# untitled01.net
KiCad netlist of a schematic drawn in EAGLE
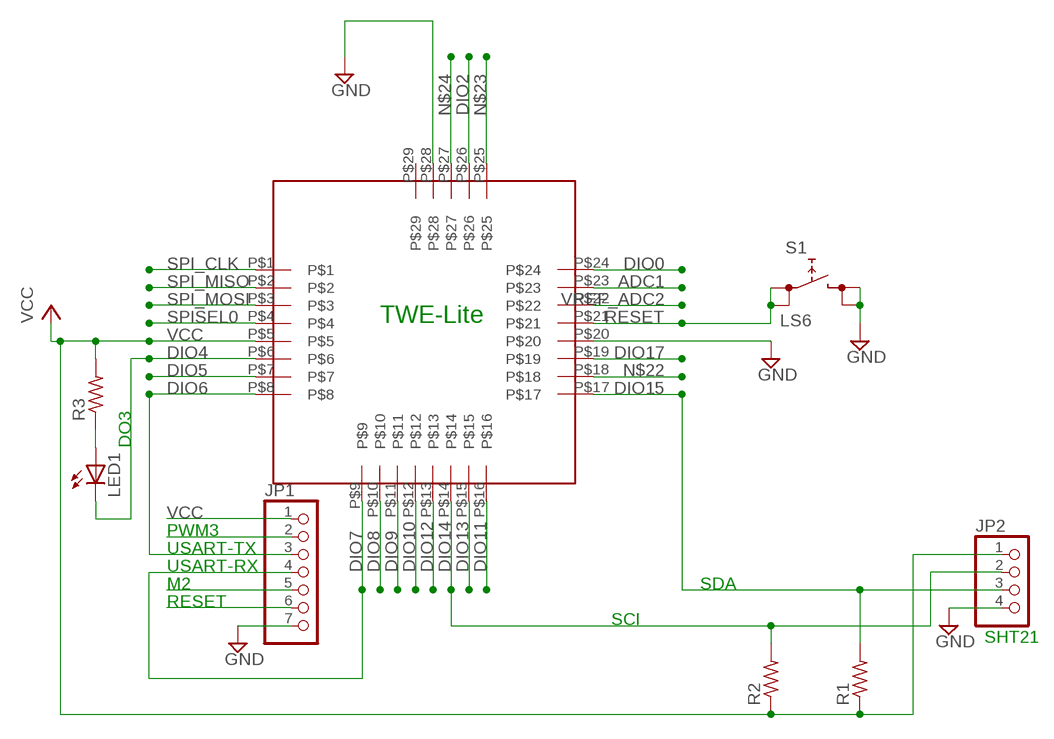
[diagram p0: schematic, sheet 1]
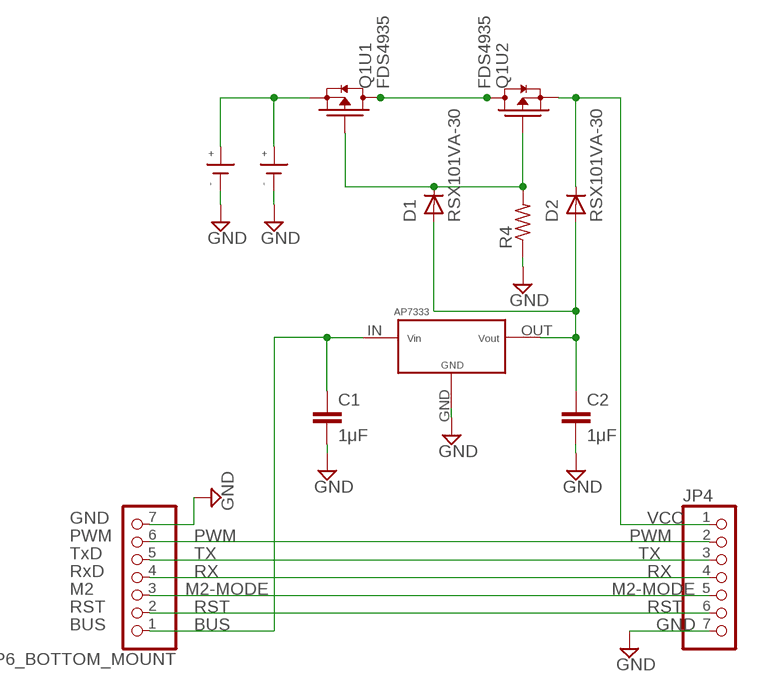
[diagram p1: schematic, sheet 2]
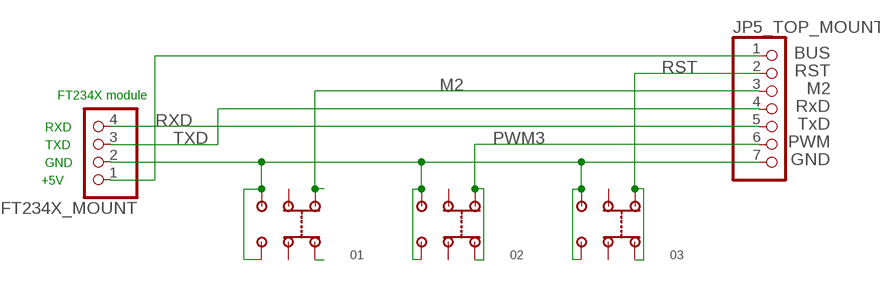
[diagram p2: schematic, sheet 3]

(export (version "E")
  (design (tool "Eeschema 10.0.6"))
  (components
    (comp (ref "01")
      (value "SSSS213202")
      (footprint "eagle-import:SSSS213202")
      (libsource (lib "eagle-import") (part "SSSS213202"))
    )
    (comp (ref "02")
      (value "SSSS213202")
      (footprint "eagle-import:SSSS213202")
      (libsource (lib "eagle-import") (part "SSSS213202"))
    )
    (comp (ref "03")
      (value "SSSS213202")
      (footprint "eagle-import:SSSS213202")
      (libsource (lib "eagle-import") (part "SSSS213202"))
    )
    (comp (ref "FT234X_MOUNT")
      (value "PINHD-1X4")
      (footprint "eagle-import:1X04")
      (libsource (lib "eagle-import") (part "PINHD-1X4"))
    )
    (comp (ref "JP5_TOP_MOUNT")
      (value "PINHD-1X7")
      (footprint "eagle-import:1X07")
      (libsource (lib "eagle-import") (part "PINHD-1X7"))
    )
    (comp (ref "JP1")
      (value "PINHD-1X7")
      (footprint "eagle-import:1X07")
      (libsource (lib "eagle-import") (part "PINHD-1X7"))
    )
    (comp (ref "JP2")
      (value "PINHD-1X4/90")
      (footprint "eagle-import:1X04_90")
      (libsource (lib "eagle-import") (part "pinhead_325_PINHD-1X4/90"))
    )
    (comp (ref "LED1")
      (value "LEDCHIP-LED0603")
      (footprint "eagle-import:CHIP-LED0603")
      (libsource (lib "eagle-import") (part "LEDCHIP-LED0603"))
    )
    (comp (ref "R1")
      (value "R-US_R0805")
      (footprint "eagle-import:R0805")
      (libsource (lib "eagle-import") (part "R-US_R0805"))
    )
    (comp (ref "R2")
      (value "R-US_R0805")
      (footprint "eagle-import:R0805")
      (libsource (lib "eagle-import") (part "R-US_R0805"))
    )
    (comp (ref "R3")
      (value "R-US_R0805")
      (footprint "eagle-import:R0805")
      (libsource (lib "eagle-import") (part "R-US_R0805"))
    )
    (comp (ref "S1")
      (value "LS6")
      (footprint "eagle-import:LS6")
      (libsource (lib "eagle-import") (part "LS6"))
    )
    (comp (ref "U$1")
      (value "LITE")
      (footprint "eagle-import:LITE")
      (libsource (lib "eagle-import") (part "LITE"))
    )
    (comp (ref "C1")
      (value "1μF")
      (footprint "eagle-import:C1608")
      (libsource (lib "eagle-import") (part "C-EUC1608"))
    )
    (comp (ref "C2")
      (value "1μF")
      (footprint "eagle-import:C1608")
      (libsource (lib "eagle-import") (part "C-EUC1608"))
    )
    (comp (ref "D1")
      (value "RSX101VA-30")
      (footprint "eagle-import:RSX101VA")
      (libsource (lib "eagle-import") (part "RSX101VA-30"))
    )
    (comp (ref "D2")
      (value "RSX101VA-30")
      (footprint "eagle-import:RSX101VA")
      (libsource (lib "eagle-import") (part "RSX101VA-30"))
    )
    (comp (ref "JP4")
      (value "PINHD-1X7")
      (footprint "eagle-import:1X07")
      (libsource (lib "eagle-import") (part "PINHD-1X7"))
    )
    (comp (ref "JP6_BOTTOM_MOUNT")
      (value "PINHD-1X7")
      (footprint "eagle-import:1X07")
      (libsource (lib "eagle-import") (part "PINHD-1X7"))
    )
    (comp (ref "Q1")
      (value "FDS4935")
      (footprint "eagle-import:SOIC(8PIN)")
      (libsource (lib "eagle-import") (part "FDS4935"))
    )
    (comp (ref "R4")
      (value "R-US_M0805")
      (footprint "eagle-import:M0805")
      (libsource (lib "eagle-import") (part "resistor_348_R-US_M0805"))
    )
    (comp (ref "U$2")
      (value "CH004-2032LF")
      (footprint "eagle-import:CH004-2032LF")
      (libsource (lib "eagle-import") (part "CH004-2032LF"))
    )
    (comp (ref "U$3")
      (value "CH004-2032LF")
      (footprint "eagle-import:CH004-2032LF")
      (libsource (lib "eagle-import") (part "CH004-2032LF"))
    )
    (comp (ref "U$5")
      (value "AP7333_SOT-23")
      (footprint "eagle-import:AP7333_SOT-23")
      (libsource (lib "eagle-import") (part "AP7333_SOT-23"))
    )
  )
  (nets
    (net (code "1") (name "ADC1") (class "Default")
      (node (ref "U$1") (pin "P$23") (pinfunction "P$23_P$23") (pintype "bidirectional"))
    )
    (net (code "2") (name "BUS") (class "Default")
      (node (ref "C1") (pin "1") (pinfunction "1_1") (pintype "passive"))
      (node (ref "JP6_BOTTOM_MOUNT") (pin "1") (pinfunction "1_1") (pintype "passive"))
      (node (ref "U$5") (pin "IN") (pinfunction "IN_IN") (pintype "input"))
    )
    (net (code "3") (name "DIO0") (class "Default")
      (node (ref "U$1") (pin "P$24") (pinfunction "P$24_P$24") (pintype "bidirectional"))
    )
    (net (code "4") (name "DIO2") (class "Default")
      (node (ref "JP1") (pin "5") (pinfunction "5_5") (pintype "passive"))
      (node (ref "U$1") (pin "P$26") (pinfunction "P$26_P$26") (pintype "bidirectional"))
    )
    (net (code "5") (name "DIO4") (class "Default")
      (node (ref "LED1") (pin "C") (pinfunction "C_C") (pintype "passive"))
      (node (ref "U$1") (pin "P$6") (pinfunction "P$6_P$6") (pintype "bidirectional"))
    )
    (net (code "6") (name "DIO5") (class "Default")
      (node (ref "U$1") (pin "P$7") (pinfunction "P$7_P$7") (pintype "bidirectional"))
    )
    (net (code "7") (name "DIO6") (class "Default")
      (node (ref "JP1") (pin "3") (pinfunction "3_3") (pintype "passive"))
      (node (ref "U$1") (pin "P$8") (pinfunction "P$8_P$8") (pintype "bidirectional"))
    )
    (net (code "8") (name "DIO7") (class "Default")
      (node (ref "JP1") (pin "4") (pinfunction "4_4") (pintype "passive"))
      (node (ref "U$1") (pin "P$9") (pinfunction "P$9_P$9") (pintype "bidirectional"))
    )
    (net (code "9") (name "DIO8") (class "Default")
      (node (ref "U$1") (pin "P$10") (pinfunction "P$10_P$10") (pintype "bidirectional"))
    )
    (net (code "10") (name "DIO9") (class "Default")
      (node (ref "U$1") (pin "P$11") (pinfunction "P$11_P$11") (pintype "bidirectional"))
    )
    (net (code "11") (name "DIO10") (class "Default")
      (node (ref "U$1") (pin "P$12") (pinfunction "P$12_P$12") (pintype "bidirectional"))
    )
    (net (code "12") (name "DIO11") (class "Default")
      (node (ref "U$1") (pin "P$16") (pinfunction "P$16_P$16") (pintype "bidirectional"))
    )
    (net (code "13") (name "DIO12") (class "Default")
      (node (ref "U$1") (pin "P$13") (pinfunction "P$13_P$13") (pintype "bidirectional"))
    )
    (net (code "14") (name "DIO13") (class "Default")
      (node (ref "U$1") (pin "P$15") (pinfunction "P$15_P$15") (pintype "bidirectional"))
    )
    (net (code "15") (name "DIO14") (class "Default")
      (node (ref "JP2") (pin "2") (pinfunction "2_2") (pintype "passive"))
      (node (ref "R2") (pin "2") (pinfunction "2_2") (pintype "passive"))
      (node (ref "U$1") (pin "P$14") (pinfunction "P$14_P$14") (pintype "bidirectional"))
    )
    (net (code "16") (name "DIO15") (class "Default")
      (node (ref "JP2") (pin "3") (pinfunction "3_3") (pintype "passive"))
      (node (ref "R1") (pin "2") (pinfunction "2_2") (pintype "passive"))
      (node (ref "U$1") (pin "P$17") (pinfunction "P$17_P$17") (pintype "bidirectional"))
    )
    (net (code "17") (name "DIO17") (class "Default")
      (node (ref "U$1") (pin "P$19") (pinfunction "P$19_P$19") (pintype "bidirectional"))
    )
    (net (code "18") (name "GND") (class "Default")
      (node (ref "01") (pin "3-1") (pinfunction "3-1_3-1") (pintype "bidirectional"))
      (node (ref "01") (pin "3-2") (pinfunction "3-2_3-2") (pintype "bidirectional"))
      (node (ref "02") (pin "3-1") (pinfunction "3-1_3-1") (pintype "bidirectional"))
      (node (ref "02") (pin "3-2") (pinfunction "3-2_3-2") (pintype "bidirectional"))
      (node (ref "03") (pin "3-1") (pinfunction "3-1_3-1") (pintype "bidirectional"))
      (node (ref "03") (pin "3-2") (pinfunction "3-2_3-2") (pintype "bidirectional"))
      (node (ref "C1") (pin "2") (pinfunction "2_2") (pintype "passive"))
      (node (ref "C2") (pin "2") (pinfunction "2_2") (pintype "passive"))
      (node (ref "FT234X_MOUNT") (pin "2") (pinfunction "2_2") (pintype "passive"))
      (node (ref "JP1") (pin "7") (pinfunction "7_7") (pintype "passive"))
      (node (ref "JP2") (pin "4") (pinfunction "4_4") (pintype "passive"))
      (node (ref "JP4") (pin "7") (pinfunction "7_7") (pintype "passive"))
      (node (ref "JP5_TOP_MOUNT") (pin "7") (pinfunction "7_7") (pintype "passive"))
      (node (ref "JP6_BOTTOM_MOUNT") (pin "7") (pinfunction "7_7") (pintype "passive"))
      (node (ref "R4") (pin "1") (pinfunction "1_1") (pintype "passive"))
      (node (ref "S1") (pin "P$3") (pinfunction "1_P$3") (pintype "passive"))
      (node (ref "S1") (pin "P$4") (pinfunction "1_P$4") (pintype "passive"))
      (node (ref "U$1") (pin "P$20") (pinfunction "P$20_P$20") (pintype "bidirectional"))
      (node (ref "U$1") (pin "P$28") (pinfunction "P$28_P$28") (pintype "bidirectional"))
      (node (ref "U$2") (pin "-") (pinfunction "-_-") (pintype "bidirectional"))
      (node (ref "U$3") (pin "-") (pinfunction "-_-") (pintype "bidirectional"))
      (node (ref "U$5") (pin "GND") (pinfunction "GND_GND") (pintype "bidirectional"))
    )
    (net (code "19") (name "M2") (class "Default")
      (node (ref "01") (pin "1-2") (pinfunction "1-2_1-2") (pintype "bidirectional"))
      (node (ref "JP5_TOP_MOUNT") (pin "3") (pinfunction "3_3") (pintype "passive"))
    )
    (net (code "20") (name "M2-MODE") (class "Default")
      (node (ref "JP4") (pin "5") (pinfunction "5_5") (pintype "passive"))
      (node (ref "JP6_BOTTOM_MOUNT") (pin "3") (pinfunction "3_3") (pintype "passive"))
    )
    (net (code "21") (name "N$22") (class "Default")
      (node (ref "U$1") (pin "P$18") (pinfunction "P$18_P$18") (pintype "bidirectional"))
    )
    (net (code "22") (name "N$23") (class "Default")
      (node (ref "U$1") (pin "P$25") (pinfunction "P$25_P$25") (pintype "bidirectional"))
    )
    (net (code "23") (name "N$24") (class "Default")
      (node (ref "U$1") (pin "P$27") (pinfunction "P$27_P$27") (pintype "bidirectional"))
    )
    (net (code "24") (name "Net-(D1-A)") (class "Default")
      (node (ref "C2") (pin "1") (pinfunction "1_1") (pintype "passive"))
      (node (ref "D1") (pin "ANODE") (pinfunction "A_ANODE") (pintype "passive"))
      (node (ref "D2") (pin "ANODE") (pinfunction "A_ANODE") (pintype "passive"))
      (node (ref "U$5") (pin "OUT") (pinfunction "OUT_OUT") (pintype "output"))
    )
    (net (code "25") (name "Net-(D1-C)") (class "Default")
      (node (ref "D1") (pin "CATHODE") (pinfunction "C_CATHODE") (pintype "passive"))
      (node (ref "Q1") (pin "2") (pinfunction "G_2") (pintype "passive"))
      (node (ref "Q1") (pin "4") (pinfunction "G_4") (pintype "passive"))
      (node (ref "R4") (pin "2") (pinfunction "2_2") (pintype "passive"))
    )
    (net (code "26") (name "Net-(FT234X_MOUNT-Pad1)") (class "Default")
      (node (ref "FT234X_MOUNT") (pin "1") (pinfunction "1_1") (pintype "passive"))
      (node (ref "JP5_TOP_MOUNT") (pin "1") (pinfunction "1_1") (pintype "passive"))
    )
    (net (code "27") (name "Net-(LED1-PadA)") (class "Default")
      (node (ref "LED1") (pin "A") (pinfunction "A_A") (pintype "passive"))
      (node (ref "R3") (pin "1") (pinfunction "1_1") (pintype "passive"))
    )
    (net (code "28") (name "Net-(Q1A-D1)") (class "Default")
      (node (ref "Q1") (pin "5") (pinfunction "D2_5") (pintype "passive"))
      (node (ref "Q1") (pin "6") (pinfunction "D1_6") (pintype "passive"))
      (node (ref "Q1") (pin "7") (pinfunction "D2_7") (pintype "passive"))
      (node (ref "Q1") (pin "8") (pinfunction "D1_8") (pintype "passive"))
    )
    (net (code "29") (name "Net-(Q1A-S)") (class "Default")
      (node (ref "Q1") (pin "1") (pinfunction "S_1") (pintype "passive"))
      (node (ref "U$2") (pin "+") (pinfunction "+_+") (pintype "bidirectional"))
      (node (ref "U$3") (pin "+") (pinfunction "+_+") (pintype "bidirectional"))
    )
    (net (code "30") (name "PWM") (class "Default")
      (node (ref "JP4") (pin "2") (pinfunction "2_2") (pintype "passive"))
      (node (ref "JP6_BOTTOM_MOUNT") (pin "6") (pinfunction "6_6") (pintype "passive"))
    )
    (net (code "31") (name "PWM3") (class "Default")
      (node (ref "02") (pin "1-1") (pinfunction "1-1_1-1") (pintype "bidirectional"))
      (node (ref "02") (pin "1-2") (pinfunction "1-2_1-2") (pintype "bidirectional"))
      (node (ref "JP5_TOP_MOUNT") (pin "6") (pinfunction "6_6") (pintype "passive"))
    )
    (net (code "32") (name "RESET") (class "Default")
      (node (ref "JP1") (pin "6") (pinfunction "6_6") (pintype "passive"))
      (node (ref "S1") (pin "P$1") (pinfunction "0_P$1") (pintype "passive"))
      (node (ref "S1") (pin "P$2") (pinfunction "0_P$2") (pintype "passive"))
      (node (ref "U$1") (pin "P$21") (pinfunction "P$21_P$21") (pintype "bidirectional"))
    )
    (net (code "33") (name "RST") (class "Default")
      (node (ref "03") (pin "1-1") (pinfunction "1-1_1-1") (pintype "bidirectional"))
      (node (ref "03") (pin "1-2") (pinfunction "1-2_1-2") (pintype "bidirectional"))
      (node (ref "JP4") (pin "6") (pinfunction "6_6") (pintype "passive"))
      (node (ref "JP5_TOP_MOUNT") (pin "2") (pinfunction "2_2") (pintype "passive"))
      (node (ref "JP6_BOTTOM_MOUNT") (pin "2") (pinfunction "2_2") (pintype "passive"))
    )
    (net (code "34") (name "RX") (class "Default")
      (node (ref "JP4") (pin "4") (pinfunction "4_4") (pintype "passive"))
      (node (ref "JP6_BOTTOM_MOUNT") (pin "4") (pinfunction "4_4") (pintype "passive"))
    )
    (net (code "35") (name "RXD") (class "Default")
      (node (ref "FT234X_MOUNT") (pin "4") (pinfunction "4_4") (pintype "passive"))
      (node (ref "JP5_TOP_MOUNT") (pin "5") (pinfunction "5_5") (pintype "passive"))
    )
    (net (code "36") (name "SPISEL0") (class "Default")
      (node (ref "U$1") (pin "P$4") (pinfunction "P$4_P$4") (pintype "bidirectional"))
    )
    (net (code "37") (name "SPI_CLK") (class "Default")
      (node (ref "U$1") (pin "P$1") (pinfunction "P$1_P$1") (pintype "bidirectional"))
    )
    (net (code "38") (name "SPI_MISO") (class "Default")
      (node (ref "JP1") (pin "2") (pinfunction "2_2") (pintype "passive"))
      (node (ref "U$1") (pin "P$2") (pinfunction "P$2_P$2") (pintype "bidirectional"))
    )
    (net (code "39") (name "SPI_MOSI") (class "Default")
      (node (ref "U$1") (pin "P$3") (pinfunction "P$3_P$3") (pintype "bidirectional"))
    )
    (net (code "40") (name "TX") (class "Default")
      (node (ref "JP4") (pin "3") (pinfunction "3_3") (pintype "passive"))
      (node (ref "JP6_BOTTOM_MOUNT") (pin "5") (pinfunction "5_5") (pintype "passive"))
    )
    (net (code "41") (name "TXD") (class "Default")
      (node (ref "FT234X_MOUNT") (pin "3") (pinfunction "3_3") (pintype "passive"))
      (node (ref "JP5_TOP_MOUNT") (pin "4") (pinfunction "4_4") (pintype "passive"))
    )
    (net (code "42") (name "VCC") (class "Default")
      (node (ref "D2") (pin "CATHODE") (pinfunction "C_CATHODE") (pintype "passive"))
      (node (ref "JP1") (pin "1") (pinfunction "1_1") (pintype "passive"))
      (node (ref "JP2") (pin "1") (pinfunction "1_1") (pintype "passive"))
      (node (ref "JP4") (pin "1") (pinfunction "1_1") (pintype "passive"))
      (node (ref "Q1") (pin "3") (pinfunction "S_3") (pintype "passive"))
      (node (ref "R1") (pin "1") (pinfunction "1_1") (pintype "passive"))
      (node (ref "R2") (pin "1") (pinfunction "1_1") (pintype "passive"))
      (node (ref "R3") (pin "2") (pinfunction "2_2") (pintype "passive"))
      (node (ref "U$1") (pin "P$5") (pinfunction "P$5_P$5") (pintype "bidirectional"))
    )
    (net (code "43") (name "VREF_ADC2") (class "Default")
      (node (ref "U$1") (pin "P$22") (pinfunction "P$22_P$22") (pintype "bidirectional"))
    )
    (net (code "44") (name "unconnected-(01-Pad1-1)") (class "Default")
      (node (ref "01") (pin "1-1") (pinfunction "1-1_1-1") (pintype "bidirectional"))
    )
    (net (code "45") (name "unconnected-(01-Pad2-1)") (class "Default")
      (node (ref "01") (pin "2-1") (pinfunction "2-1_2-1") (pintype "bidirectional"))
    )
    (net (code "46") (name "unconnected-(01-Pad2-2)") (class "Default")
      (node (ref "01") (pin "2-2") (pinfunction "2-2_2-2") (pintype "bidirectional"))
    )
    (net (code "47") (name "unconnected-(02-Pad2-1)") (class "Default")
      (node (ref "02") (pin "2-1") (pinfunction "2-1_2-1") (pintype "bidirectional"))
    )
    (net (code "48") (name "unconnected-(02-Pad2-2)") (class "Default")
      (node (ref "02") (pin "2-2") (pinfunction "2-2_2-2") (pintype "bidirectional"))
    )
    (net (code "49") (name "unconnected-(03-Pad2-1)") (class "Default")
      (node (ref "03") (pin "2-1") (pinfunction "2-1_2-1") (pintype "bidirectional"))
    )
    (net (code "50") (name "unconnected-(03-Pad2-2)") (class "Default")
      (node (ref "03") (pin "2-2") (pinfunction "2-2_2-2") (pintype "bidirectional"))
    )
    (net (code "51") (name "unconnected-(U$1-PadP$29)") (class "Default")
      (node (ref "U$1") (pin "P$29") (pinfunction "P$29_P$29") (pintype "bidirectional"))
    )
  )
)
